# stm32_StepInveter_1904_01.net
KiCad netlist of a schematic drawn in EAGLE
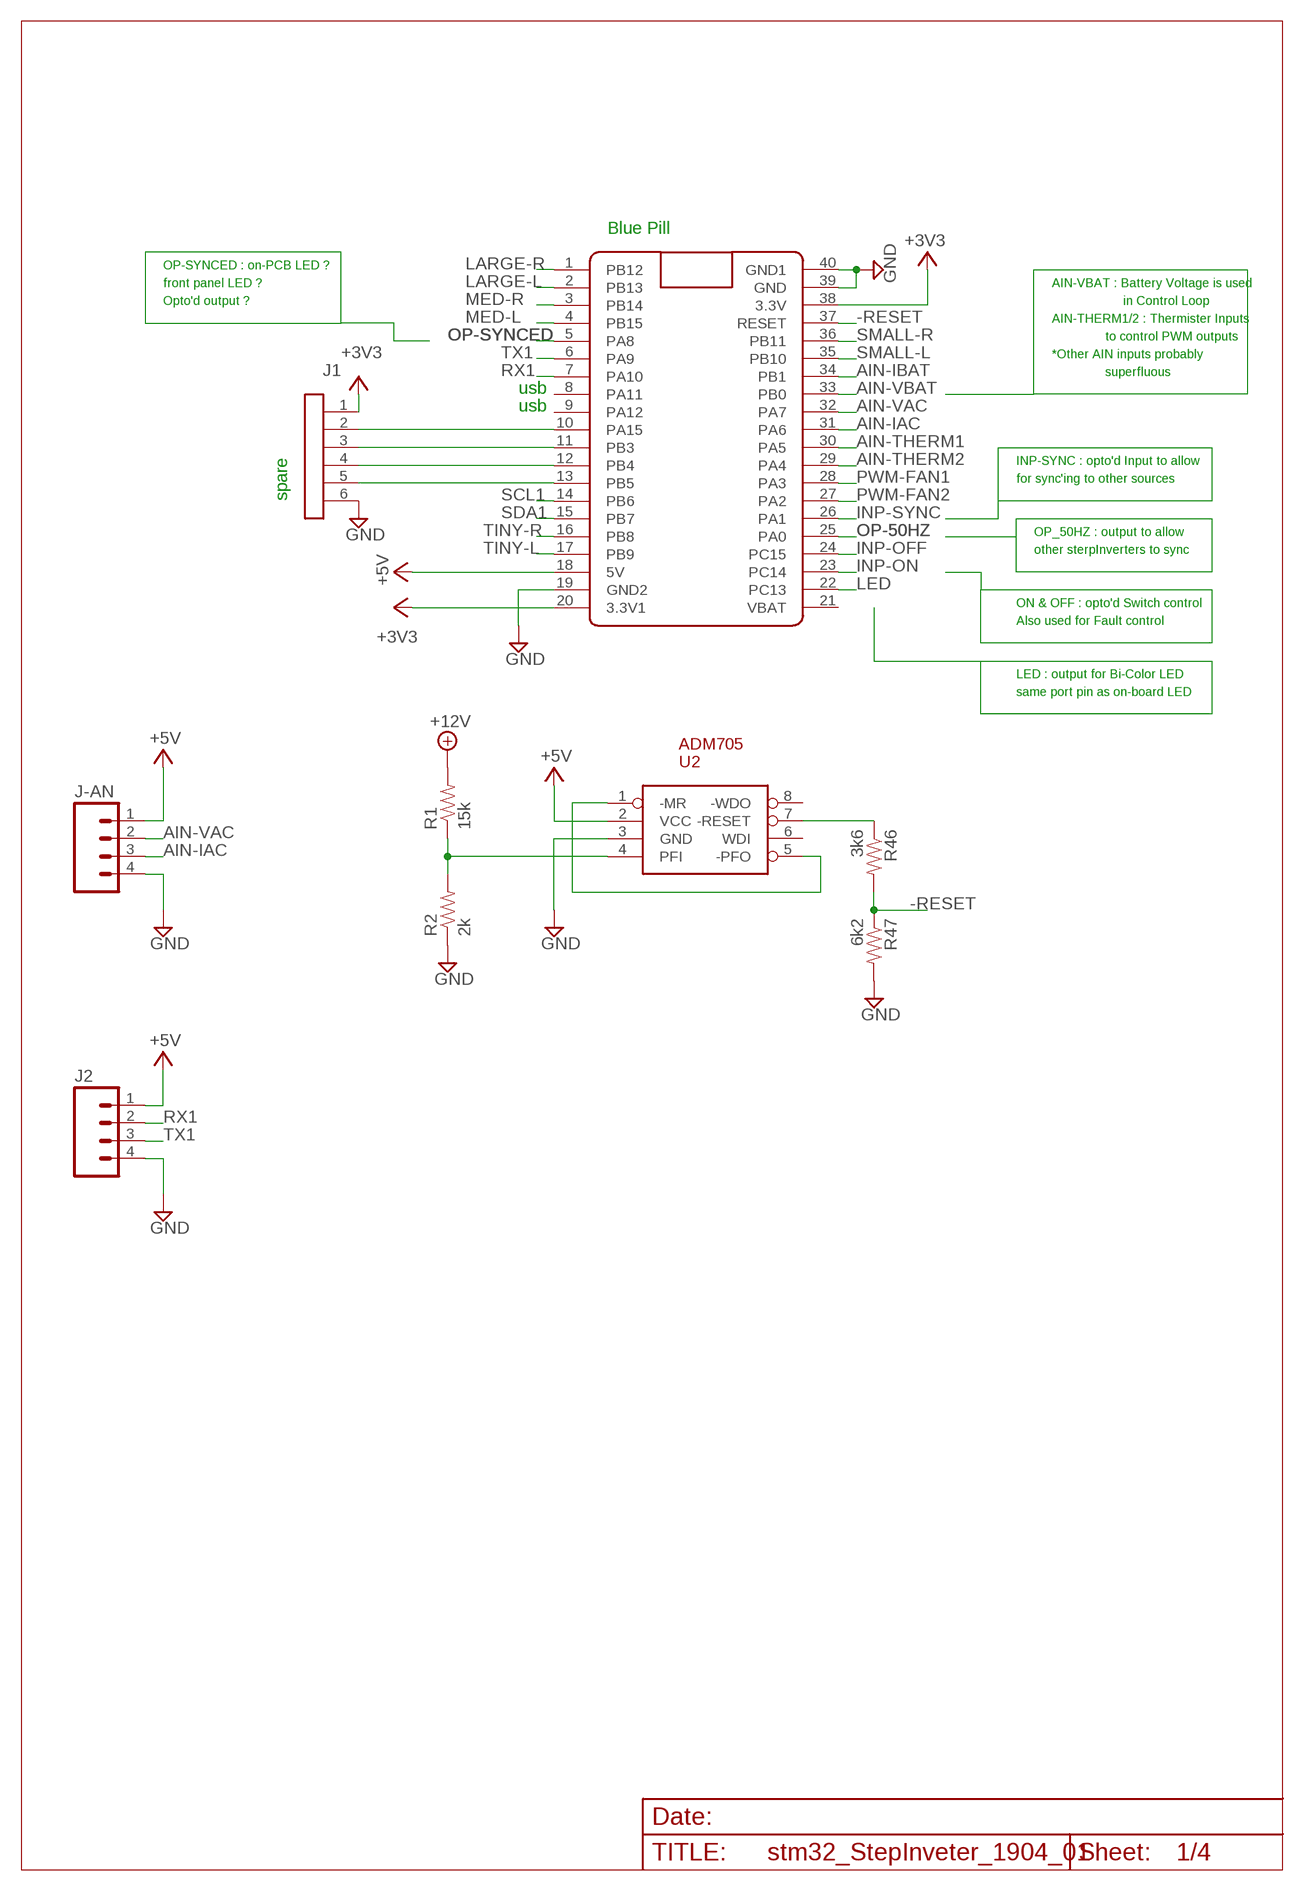
[diagram p0: schematic, sheet 1]
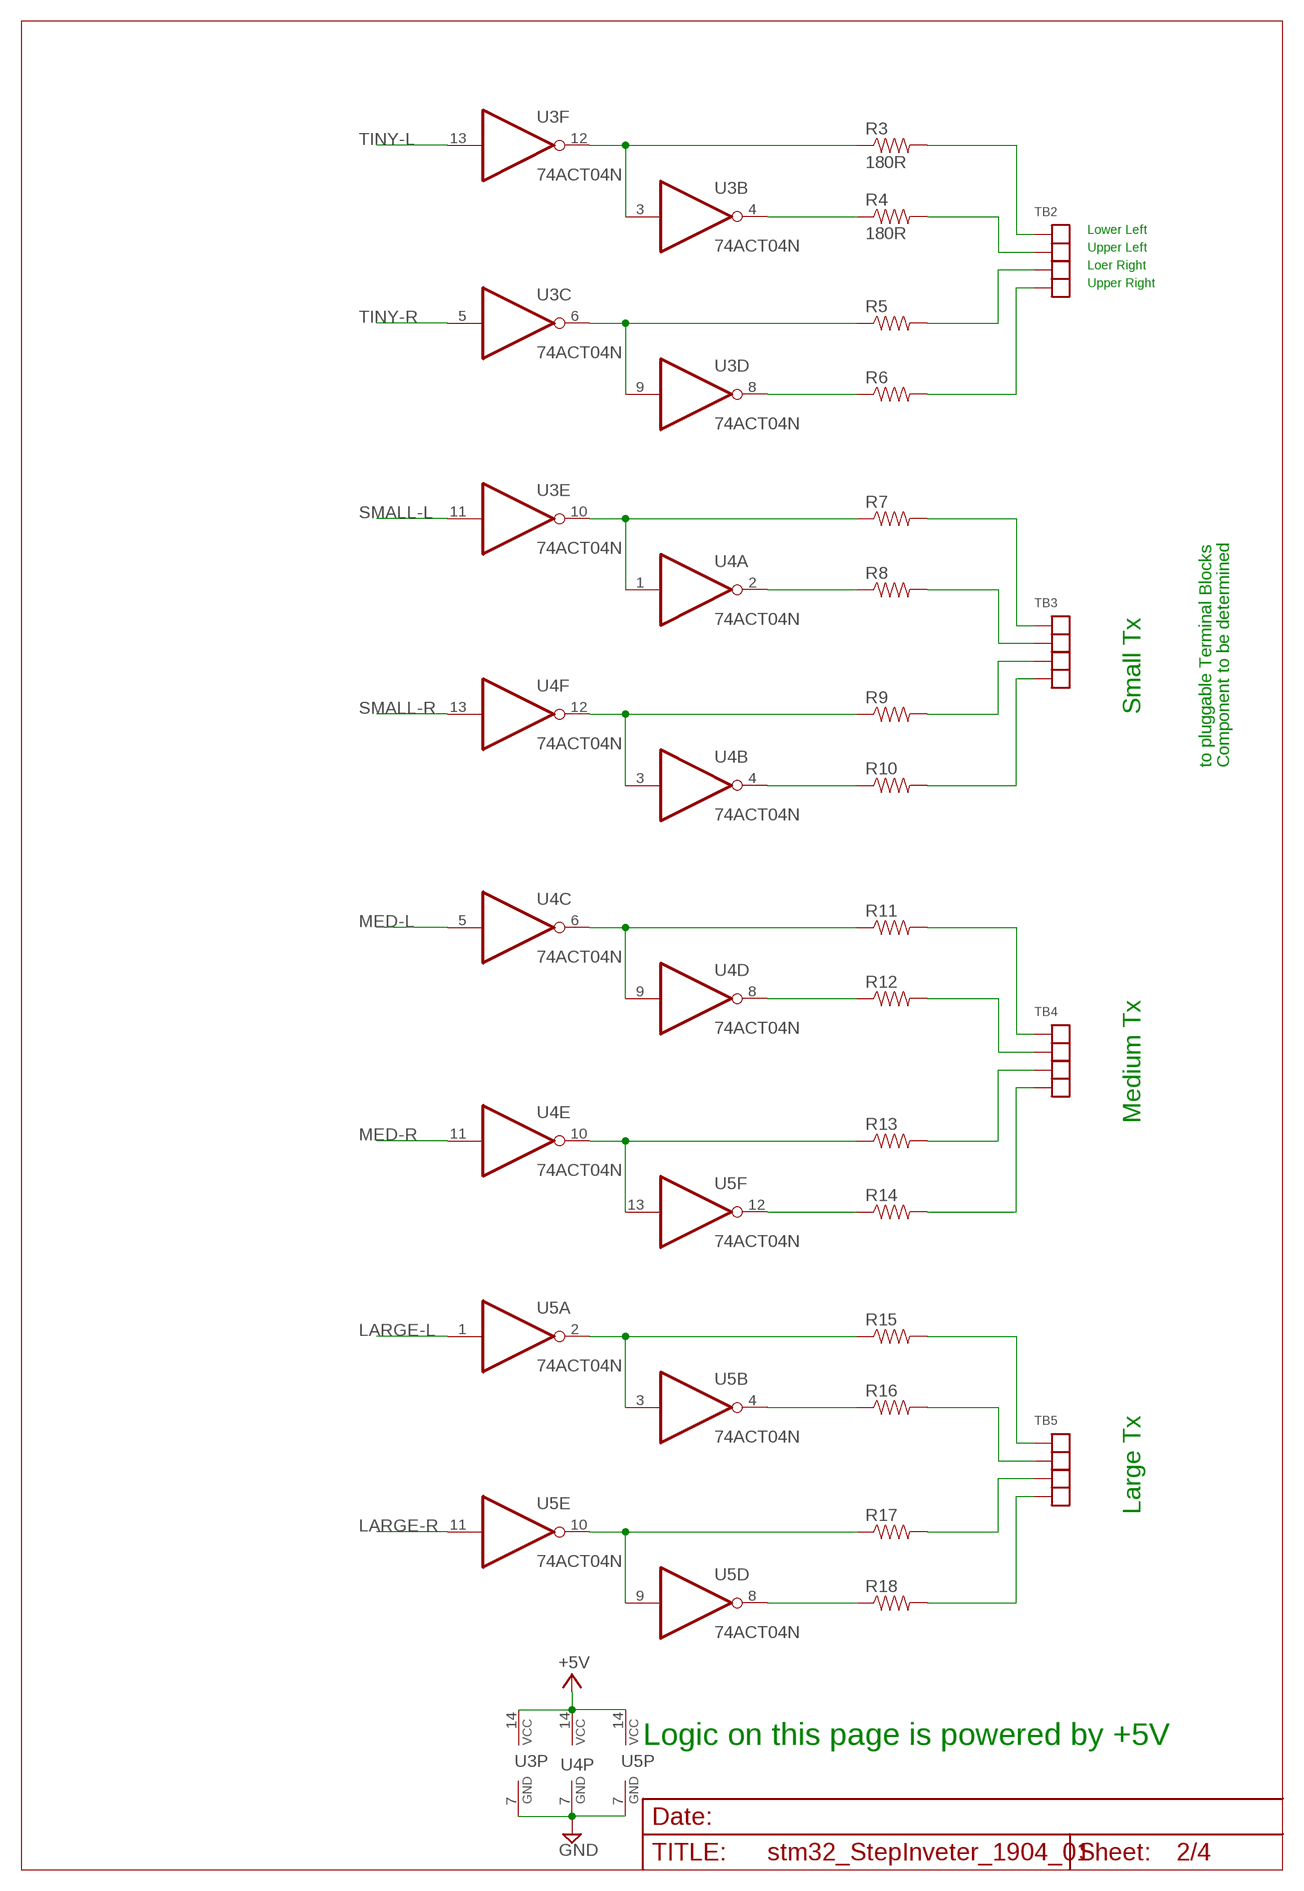
[diagram p1: schematic, sheet 2]
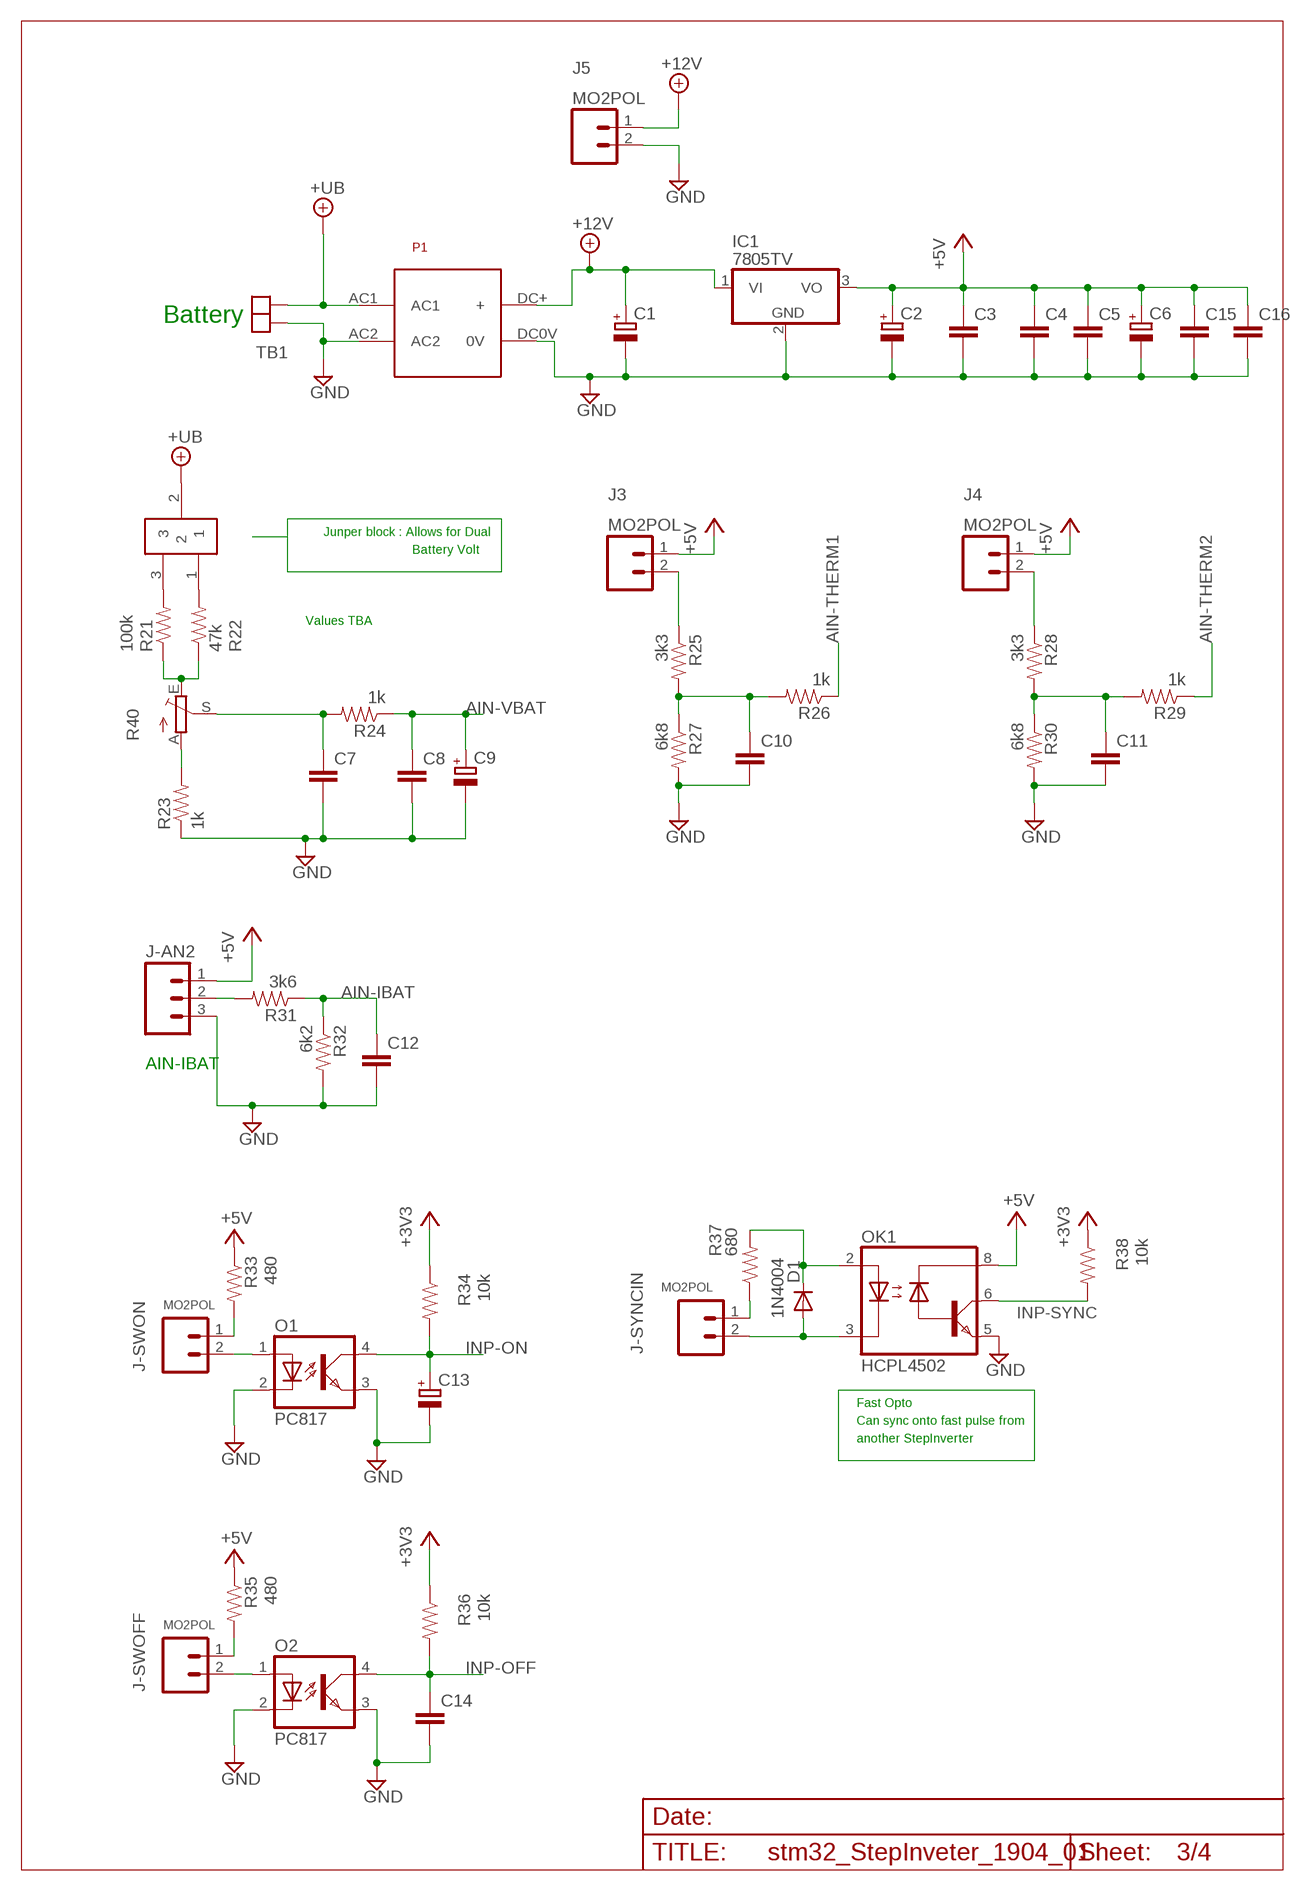
[diagram p2: schematic, sheet 3]
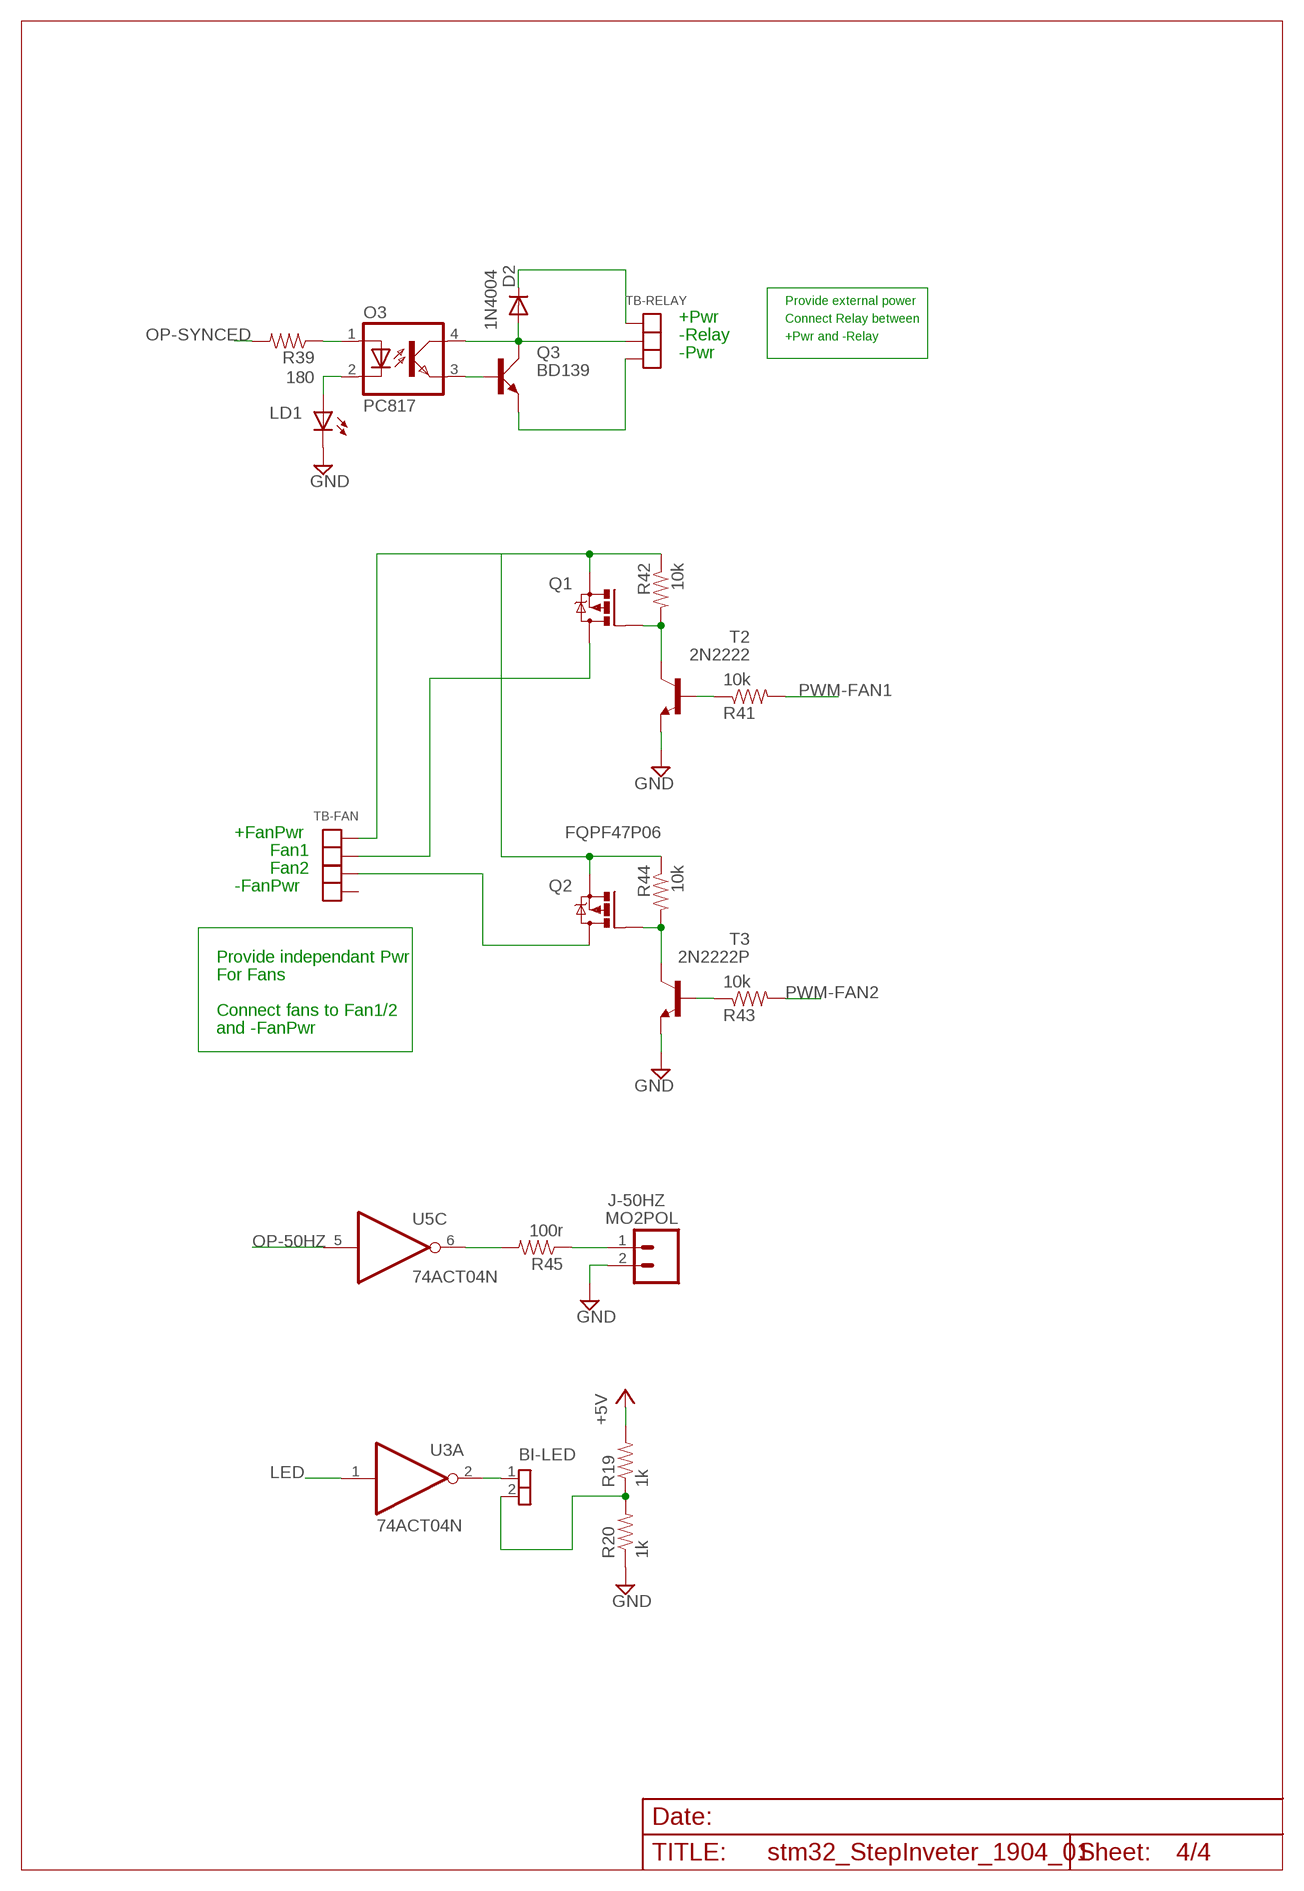
[diagram p3: schematic, sheet 4]

(export (version "E")
  (design (tool "Eeschema 10.0.6"))
  (components
    (comp (ref "J-AN")
      (value "SIL4")
      (footprint "eagle-import:SIL4")
      (libsource (lib "eagle-import") (part "SIL4"))
    )
    (comp (ref "J1")
      (value "SIL-6")
      (footprint "eagle-import:SIL6")
      (libsource (lib "eagle-import") (part "SIL-6"))
    )
    (comp (ref "J2")
      (value "SIL4")
      (footprint "eagle-import:SIL4")
      (libsource (lib "eagle-import") (part "SIL4"))
    )
    (comp (ref "R1")
      (value "15k")
      (footprint "eagle-import:AXIAL-0.4")
      (libsource (lib "eagle-import") (part "R4"))
    )
    (comp (ref "R2")
      (value "2k")
      (footprint "eagle-import:AXIAL-0.4")
      (libsource (lib "eagle-import") (part "R4"))
    )
    (comp (ref "R46")
      (value "3k6")
      (footprint "eagle-import:AXIAL-0.4")
      (libsource (lib "eagle-import") (part "R4"))
    )
    (comp (ref "R47")
      (value "6k2")
      (footprint "eagle-import:AXIAL-0.4")
      (libsource (lib "eagle-import") (part "R4"))
    )
    (comp (ref "U$1")
      (value "BLUE_PILL")
      (footprint "eagle-import:BLUE_PILL_CLEAN")
      (libsource (lib "eagle-import") (part "BLUE_PILL"))
    )
    (comp (ref "U2")
      (value "ADM705")
      (footprint "eagle-import:DIL08")
      (libsource (lib "eagle-import") (part "ADM705"))
    )
    (comp (ref "C1")
      (value "CPOL-EUE5-8.5")
      (footprint "eagle-import:E5-8,5")
      (libsource (lib "eagle-import") (part "CPOL-EUE5-8.5"))
    )
    (comp (ref "C2")
      (value "CPOL-EUE2.5-5")
      (footprint "eagle-import:E2,5-5")
      (libsource (lib "eagle-import") (part "CPOL-EUE2.5-5"))
    )
    (comp (ref "C3")
      (value "BCAP")
      (footprint "eagle-import:BCAP")
      (libsource (lib "eagle-import") (part "BCAP"))
    )
    (comp (ref "C4")
      (value "BCAP")
      (footprint "eagle-import:BCAP")
      (libsource (lib "eagle-import") (part "BCAP"))
    )
    (comp (ref "C5")
      (value "BCAP")
      (footprint "eagle-import:BCAP")
      (libsource (lib "eagle-import") (part "BCAP"))
    )
    (comp (ref "C6")
      (value "CPOL-EUE2.5-5")
      (footprint "eagle-import:E2,5-5")
      (libsource (lib "eagle-import") (part "CPOL-EUE2.5-5"))
    )
    (comp (ref "C7")
      (value "BCAP")
      (footprint "eagle-import:BCAP")
      (libsource (lib "eagle-import") (part "BCAP"))
    )
    (comp (ref "C8")
      (value "BCAP")
      (footprint "eagle-import:BCAP")
      (libsource (lib "eagle-import") (part "BCAP"))
    )
    (comp (ref "C9")
      (value "CPOL-EUE2.5-5")
      (footprint "eagle-import:E2,5-5")
      (libsource (lib "eagle-import") (part "CPOL-EUE2.5-5"))
    )
    (comp (ref "C10")
      (value "BCAP")
      (footprint "eagle-import:BCAP")
      (libsource (lib "eagle-import") (part "BCAP"))
    )
    (comp (ref "C11")
      (value "BCAP")
      (footprint "eagle-import:BCAP")
      (libsource (lib "eagle-import") (part "BCAP"))
    )
    (comp (ref "C12")
      (value "BCAP")
      (footprint "eagle-import:BCAP")
      (libsource (lib "eagle-import") (part "BCAP"))
    )
    (comp (ref "C13")
      (value "CPOL-EUE2.5-6")
      (footprint "eagle-import:E2,5-6")
      (libsource (lib "eagle-import") (part "CPOL-EUE2.5-6"))
    )
    (comp (ref "C14")
      (value "BCAP")
      (footprint "eagle-import:BCAP")
      (libsource (lib "eagle-import") (part "BCAP"))
    )
    (comp (ref "C15")
      (value "BCAP")
      (footprint "eagle-import:BCAP")
      (libsource (lib "eagle-import") (part "BCAP"))
    )
    (comp (ref "C16")
      (value "BCAP")
      (footprint "eagle-import:BCAP")
      (libsource (lib "eagle-import") (part "BCAP"))
    )
    (comp (ref "D1")
      (value "1N4004")
      (footprint "eagle-import:DO41-10")
      (libsource (lib "eagle-import") (part "1N4004"))
    )
    (comp (ref "IC1")
      (value "7805TV")
      (footprint "eagle-import:TO220V")
      (libsource (lib "eagle-import") (part "78TV05"))
    )
    (comp (ref "J-AN2")
      (value "MO3POL")
      (footprint "eagle-import:MOLEX-3")
      (libsource (lib "eagle-import") (part "MO3POL"))
    )
    (comp (ref "J-SWOFF")
      (value "MO2POL")
      (footprint "eagle-import:MOLEX-1X2")
      (libsource (lib "eagle-import") (part "MO2POL"))
    )
    (comp (ref "J-SWON")
      (value "MO2POL")
      (footprint "eagle-import:MOLEX-1X2")
      (libsource (lib "eagle-import") (part "MO2POL"))
    )
    (comp (ref "J-SYNCIN")
      (value "MO2POL")
      (footprint "eagle-import:MOLEX-1X2")
      (libsource (lib "eagle-import") (part "MO2POL"))
    )
    (comp (ref "J3")
      (value "MO2POL")
      (footprint "eagle-import:MOLEX-1X2")
      (libsource (lib "eagle-import") (part "MO2POL"))
    )
    (comp (ref "J4")
      (value "MO2POL")
      (footprint "eagle-import:MOLEX-1X2")
      (libsource (lib "eagle-import") (part "MO2POL"))
    )
    (comp (ref "J5")
      (value "MO2POL")
      (footprint "eagle-import:MOLEX-1X2")
      (libsource (lib "eagle-import") (part "MO2POL"))
    )
    (comp (ref "JP1")
      (value "JP1X3")
      (footprint "eagle-import:JP1X3")
      (libsource (lib "eagle-import") (part "JP1X3"))
    )
    (comp (ref "O1")
      (value "PC817")
      (footprint "eagle-import:DIL04")
      (fields (field (name "MPN") "PC817X4J000F"))
      (libsource (lib "eagle-import") (part "PC817"))
    )
    (comp (ref "O2")
      (value "PC817")
      (footprint "eagle-import:DIL04")
      (fields (field (name "MPN") "PC817X4J000F"))
      (libsource (lib "eagle-import") (part "PC817"))
    )
    (comp (ref "OK1")
      (value "HCPL4502")
      (footprint "eagle-import:DIL08")
      (fields (field (name "MF") "AGILENT TECHNOLOGIES") (field (name "MPN") "HCPL-4502-000E"))
      (libsource (lib "eagle-import") (part "HCPL4502"))
    )
    (comp (ref "P1")
      (value "ACDC")
      (footprint "eagle-import:ACDC")
      (libsource (lib "eagle-import") (part "ACDC"))
    )
    (comp (ref "R21")
      (value "100k")
      (footprint "eagle-import:AXIAL-0.4")
      (libsource (lib "eagle-import") (part "R4"))
    )
    (comp (ref "R22")
      (value "47k")
      (footprint "eagle-import:AXIAL-0.4")
      (libsource (lib "eagle-import") (part "R4"))
    )
    (comp (ref "R23")
      (value "1k")
      (footprint "eagle-import:AXIAL-0.4")
      (libsource (lib "eagle-import") (part "R4"))
    )
    (comp (ref "R24")
      (value "1k")
      (footprint "eagle-import:AXIAL-0.4")
      (libsource (lib "eagle-import") (part "R4"))
    )
    (comp (ref "R25")
      (value "3k3")
      (footprint "eagle-import:AXIAL-0.4")
      (libsource (lib "eagle-import") (part "R4"))
    )
    (comp (ref "R26")
      (value "1k")
      (footprint "eagle-import:AXIAL-0.4")
      (libsource (lib "eagle-import") (part "R4"))
    )
    (comp (ref "R27")
      (value "6k8")
      (footprint "eagle-import:AXIAL-0.4")
      (libsource (lib "eagle-import") (part "R4"))
    )
    (comp (ref "R28")
      (value "3k3")
      (footprint "eagle-import:AXIAL-0.4")
      (libsource (lib "eagle-import") (part "R4"))
    )
    (comp (ref "R29")
      (value "1k")
      (footprint "eagle-import:AXIAL-0.4")
      (libsource (lib "eagle-import") (part "R4"))
    )
    (comp (ref "R30")
      (value "6k8")
      (footprint "eagle-import:AXIAL-0.4")
      (libsource (lib "eagle-import") (part "R4"))
    )
    (comp (ref "R31")
      (value "3k6")
      (footprint "eagle-import:AXIAL-0.4")
      (libsource (lib "eagle-import") (part "R4"))
    )
    (comp (ref "R32")
      (value "6k2")
      (footprint "eagle-import:AXIAL-0.4")
      (libsource (lib "eagle-import") (part "R4"))
    )
    (comp (ref "R33")
      (value "480")
      (footprint "eagle-import:AXIAL-0.4")
      (libsource (lib "eagle-import") (part "R4"))
    )
    (comp (ref "R34")
      (value "10k")
      (footprint "eagle-import:AXIAL-0.4")
      (libsource (lib "eagle-import") (part "R4"))
    )
    (comp (ref "R35")
      (value "480")
      (footprint "eagle-import:AXIAL-0.4")
      (libsource (lib "eagle-import") (part "R4"))
    )
    (comp (ref "R36")
      (value "10k")
      (footprint "eagle-import:AXIAL-0.4")
      (libsource (lib "eagle-import") (part "R4"))
    )
    (comp (ref "R37")
      (value "680")
      (footprint "eagle-import:AXIAL-0.4")
      (libsource (lib "eagle-import") (part "R4"))
    )
    (comp (ref "R38")
      (value "10k")
      (footprint "eagle-import:AXIAL-0.4")
      (libsource (lib "eagle-import") (part "R4"))
    )
    (comp (ref "R40")
      (value "TRIM_EU-B64Y")
      (footprint "eagle-import:B64Y")
      (libsource (lib "eagle-import") (part "TRIM_EU-B64Y"))
    )
    (comp (ref "TB1")
      (value "TB2381")
      (footprint "eagle-import:TB-KF2EDG381-2P")
      (libsource (lib "eagle-import") (part "TB2381"))
    )
    (comp (ref "BI-LED")
      (value "SIL-2")
      (footprint "eagle-import:JP1")
      (libsource (lib "eagle-import") (part "SIL-2"))
    )
    (comp (ref "D2")
      (value "1N4004")
      (footprint "eagle-import:DO41-10")
      (libsource (lib "eagle-import") (part "1N4004"))
    )
    (comp (ref "J-50HZ")
      (value "MO2POL")
      (footprint "eagle-import:MOLEX-1X2")
      (libsource (lib "eagle-import") (part "MO2POL"))
    )
    (comp (ref "LD1")
      (value "LED3MM")
      (footprint "eagle-import:LED3MM")
      (libsource (lib "eagle-import") (part "LED3MM"))
    )
    (comp (ref "O3")
      (value "PC817")
      (footprint "eagle-import:DIL04")
      (fields (field (name "MPN") "PC817X4J000F"))
      (libsource (lib "eagle-import") (part "PC817"))
    )
    (comp (ref "Q1")
      (value "MOSFET-PCHFQPF47P06")
      (footprint "eagle-import:TO220BV")
      (libsource (lib "eagle-import") (part "MOSFET-PCHFQPF47P06"))
    )
    (comp (ref "Q2")
      (value "FQPF47P06")
      (footprint "eagle-import:TO220BV")
      (libsource (lib "eagle-import") (part "MOSFET-PCHFQPF47P06"))
    )
    (comp (ref "Q3")
      (value "BD139")
      (footprint "eagle-import:TO126AV")
      (libsource (lib "eagle-import") (part "BD139"))
    )
    (comp (ref "R19")
      (value "1k")
      (footprint "eagle-import:AXIAL-0.4")
      (libsource (lib "eagle-import") (part "R4"))
    )
    (comp (ref "R20")
      (value "1k")
      (footprint "eagle-import:AXIAL-0.4")
      (libsource (lib "eagle-import") (part "R4"))
    )
    (comp (ref "R39")
      (value "180")
      (footprint "eagle-import:AXIAL-0.4")
      (libsource (lib "eagle-import") (part "R4"))
    )
    (comp (ref "R41")
      (value "10k")
      (footprint "eagle-import:AXIAL-0.4")
      (libsource (lib "eagle-import") (part "R4"))
    )
    (comp (ref "R42")
      (value "10k")
      (footprint "eagle-import:AXIAL-0.4")
      (libsource (lib "eagle-import") (part "R4"))
    )
    (comp (ref "R43")
      (value "10k")
      (footprint "eagle-import:AXIAL-0.4")
      (libsource (lib "eagle-import") (part "R4"))
    )
    (comp (ref "R44")
      (value "10k")
      (footprint "eagle-import:AXIAL-0.4")
      (libsource (lib "eagle-import") (part "R4"))
    )
    (comp (ref "R45")
      (value "100r")
      (footprint "eagle-import:AXIAL-0.4")
      (libsource (lib "eagle-import") (part "R4"))
    )
    (comp (ref "T2")
      (value "2N2222")
      (footprint "eagle-import:TO92_")
      (libsource (lib "eagle-import") (part "2N2222P"))
    )
    (comp (ref "T3")
      (value "2N2222P")
      (footprint "eagle-import:TO92_")
      (libsource (lib "eagle-import") (part "2N2222P"))
    )
    (comp (ref "TB-FAN")
      (value "TB4")
      (footprint "eagle-import:TB-KF2EDG381-4P")
      (libsource (lib "eagle-import") (part "TB4"))
    )
    (comp (ref "TB-RELAY")
      (value "TB3381")
      (footprint "eagle-import:TB-KF2EDG381-3P")
      (libsource (lib "eagle-import") (part "TB3381"))
    )
    (comp (ref "U3")
      (value "74ACT04N")
      (footprint "eagle-import:DIL14")
      (libsource (lib "eagle-import") (part "7404NACT"))
    )
    (comp (ref "U5")
      (value "74ACT04N")
      (footprint "eagle-import:DIL14")
      (libsource (lib "eagle-import") (part "7404NACT"))
    )
    (comp (ref "R3")
      (value "180R")
      (footprint "eagle-import:AXIAL-0.4")
      (libsource (lib "eagle-import") (part "R4"))
    )
    (comp (ref "R4")
      (value "180R")
      (footprint "eagle-import:AXIAL-0.4")
      (libsource (lib "eagle-import") (part "R4"))
    )
    (comp (ref "R5")
      (value "R4")
      (footprint "eagle-import:AXIAL-0.4")
      (libsource (lib "eagle-import") (part "R4"))
    )
    (comp (ref "R6")
      (value "R4")
      (footprint "eagle-import:AXIAL-0.4")
      (libsource (lib "eagle-import") (part "R4"))
    )
    (comp (ref "R7")
      (value "R4")
      (footprint "eagle-import:AXIAL-0.4")
      (libsource (lib "eagle-import") (part "R4"))
    )
    (comp (ref "R8")
      (value "R4")
      (footprint "eagle-import:AXIAL-0.4")
      (libsource (lib "eagle-import") (part "R4"))
    )
    (comp (ref "R9")
      (value "R4")
      (footprint "eagle-import:AXIAL-0.4")
      (libsource (lib "eagle-import") (part "R4"))
    )
    (comp (ref "R10")
      (value "R4")
      (footprint "eagle-import:AXIAL-0.4")
      (libsource (lib "eagle-import") (part "R4"))
    )
    (comp (ref "R11")
      (value "R4")
      (footprint "eagle-import:AXIAL-0.4")
      (libsource (lib "eagle-import") (part "R4"))
    )
    (comp (ref "R12")
      (value "R4")
      (footprint "eagle-import:AXIAL-0.4")
      (libsource (lib "eagle-import") (part "R4"))
    )
    (comp (ref "R13")
      (value "R4")
      (footprint "eagle-import:AXIAL-0.4")
      (libsource (lib "eagle-import") (part "R4"))
    )
    (comp (ref "R14")
      (value "R4")
      (footprint "eagle-import:AXIAL-0.4")
      (libsource (lib "eagle-import") (part "R4"))
    )
    (comp (ref "R15")
      (value "R4")
      (footprint "eagle-import:AXIAL-0.4")
      (libsource (lib "eagle-import") (part "R4"))
    )
    (comp (ref "R16")
      (value "R4")
      (footprint "eagle-import:AXIAL-0.4")
      (libsource (lib "eagle-import") (part "R4"))
    )
    (comp (ref "R17")
      (value "R4")
      (footprint "eagle-import:AXIAL-0.4")
      (libsource (lib "eagle-import") (part "R4"))
    )
    (comp (ref "R18")
      (value "R4")
      (footprint "eagle-import:AXIAL-0.4")
      (libsource (lib "eagle-import") (part "R4"))
    )
    (comp (ref "TB2")
      (value "TB4381_SIL")
      (footprint "eagle-import:TB-381-SIL-4P")
      (libsource (lib "eagle-import") (part "TB4381_SIL"))
    )
    (comp (ref "TB3")
      (value "TB4381_SIL")
      (footprint "eagle-import:TB-381-SIL-4P")
      (libsource (lib "eagle-import") (part "TB4381_SIL"))
    )
    (comp (ref "TB4")
      (value "TB4381_SIL")
      (footprint "eagle-import:TB-381-SIL-4P")
      (libsource (lib "eagle-import") (part "TB4381_SIL"))
    )
    (comp (ref "TB5")
      (value "TB4381_SIL")
      (footprint "eagle-import:TB-381-SIL-4P")
      (libsource (lib "eagle-import") (part "TB4381_SIL"))
    )
    (comp (ref "U4")
      (value "74ACT04N")
      (footprint "eagle-import:DIL14")
      (libsource (lib "eagle-import") (part "7404NACT"))
    )
  )
  (nets
    (net (code "1") (name "+3V3") (class "Default")
      (node (ref "J1") (pin "1") (pinfunction "P$1_1") (pintype "bidirectional"))
      (node (ref "R34") (pin "P$1") (pinfunction "1_P$1") (pintype "passive"))
      (node (ref "R36") (pin "P$1") (pinfunction "1_P$1") (pintype "passive"))
      (node (ref "R38") (pin "P$1") (pinfunction "1_P$1") (pintype "passive"))
      (node (ref "U$1") (pin "20") (pinfunction "3.3V1_20") (pintype "bidirectional"))
      (node (ref "U$1") (pin "38") (pinfunction "3.3V_38") (pintype "bidirectional"))
    )
    (net (code "2") (name "+5V") (class "Default")
      (node (ref "C15") (pin "1") (pinfunction "1_1") (pintype "passive"))
      (node (ref "C16") (pin "1") (pinfunction "1_1") (pintype "passive"))
      (node (ref "C2") (pin "+") (pinfunction "+_+") (pintype "passive"))
      (node (ref "C3") (pin "1") (pinfunction "1_1") (pintype "passive"))
      (node (ref "C4") (pin "1") (pinfunction "1_1") (pintype "passive"))
      (node (ref "C5") (pin "1") (pinfunction "1_1") (pintype "passive"))
      (node (ref "C6") (pin "+") (pinfunction "+_+") (pintype "passive"))
      (node (ref "IC1") (pin "3") (pinfunction "VO_3") (pintype "passive"))
      (node (ref "J-AN") (pin "1") (pinfunction "1_1") (pintype "passive"))
      (node (ref "J-AN2") (pin "1") (pinfunction "1_1") (pintype "passive"))
      (node (ref "J2") (pin "1") (pinfunction "1_1") (pintype "passive"))
      (node (ref "J3") (pin "1") (pinfunction "1_1") (pintype "passive"))
      (node (ref "J4") (pin "1") (pinfunction "1_1") (pintype "passive"))
      (node (ref "OK1") (pin "8") (pinfunction "VCC_8") (pintype "passive"))
      (node (ref "R19") (pin "P$2") (pinfunction "2_P$2") (pintype "passive"))
      (node (ref "R33") (pin "P$1") (pinfunction "1_P$1") (pintype "passive"))
      (node (ref "R35") (pin "P$1") (pinfunction "1_P$1") (pintype "passive"))
      (node (ref "U$1") (pin "18") (pinfunction "5V_18") (pintype "bidirectional"))
      (node (ref "U2") (pin "2") (pinfunction "VCC_2") (pintype "bidirectional"))
      (node (ref "U3") (pin "14") (pinfunction "VCC_14") (pintype "power_in"))
      (node (ref "U4") (pin "14") (pinfunction "VCC_14") (pintype "power_in"))
      (node (ref "U5") (pin "14") (pinfunction "VCC_14") (pintype "power_in"))
    )
    (net (code "3") (name "+12V") (class "Default")
      (node (ref "C1") (pin "+") (pinfunction "+_+") (pintype "passive"))
      (node (ref "IC1") (pin "1") (pinfunction "VI_1") (pintype "input"))
      (node (ref "J5") (pin "1") (pinfunction "1_1") (pintype "passive"))
      (node (ref "P1") (pin "DC+") (pinfunction "+_DC+") (pintype "bidirectional"))
      (node (ref "R1") (pin "P$2") (pinfunction "2_P$2") (pintype "passive"))
    )
    (net (code "4") (name "+UB") (class "Default")
      (node (ref "JP1") (pin "2") (pinfunction "2_2") (pintype "bidirectional"))
      (node (ref "P1") (pin "AC1") (pinfunction "AC1_AC1") (pintype "bidirectional"))
      (node (ref "TB1") (pin "1") (pinfunction "1_1") (pintype "bidirectional"))
    )
    (net (code "5") (name "-RESET") (class "Default")
      (node (ref "R46") (pin "P$2") (pinfunction "2_P$2") (pintype "passive"))
      (node (ref "R47") (pin "P$1") (pinfunction "1_P$1") (pintype "passive"))
      (node (ref "U$1") (pin "37") (pinfunction "RESET_37") (pintype "bidirectional"))
    )
    (net (code "6") (name "AIN-IAC") (class "Default")
      (node (ref "J-AN") (pin "3") (pinfunction "3_3") (pintype "passive"))
      (node (ref "U$1") (pin "31") (pinfunction "PA6_31") (pintype "bidirectional"))
    )
    (net (code "7") (name "AIN-IBAT") (class "Default")
      (node (ref "C12") (pin "1") (pinfunction "1_1") (pintype "passive"))
      (node (ref "R31") (pin "P$1") (pinfunction "1_P$1") (pintype "passive"))
      (node (ref "R32") (pin "P$1") (pinfunction "1_P$1") (pintype "passive"))
      (node (ref "U$1") (pin "34") (pinfunction "PB1_34") (pintype "bidirectional"))
    )
    (net (code "8") (name "AIN-THERM1") (class "Default")
      (node (ref "R26") (pin "P$1") (pinfunction "1_P$1") (pintype "passive"))
      (node (ref "U$1") (pin "30") (pinfunction "PA5_30") (pintype "bidirectional"))
    )
    (net (code "9") (name "AIN-THERM2") (class "Default")
      (node (ref "R29") (pin "P$1") (pinfunction "1_P$1") (pintype "passive"))
      (node (ref "U$1") (pin "29") (pinfunction "PA4_29") (pintype "bidirectional"))
    )
    (net (code "10") (name "AIN-VAC") (class "Default")
      (node (ref "J-AN") (pin "2") (pinfunction "2_2") (pintype "passive"))
      (node (ref "U$1") (pin "32") (pinfunction "PA7_32") (pintype "bidirectional"))
    )
    (net (code "11") (name "AIN-VBAT") (class "Default")
      (node (ref "C8") (pin "1") (pinfunction "1_1") (pintype "passive"))
      (node (ref "C9") (pin "+") (pinfunction "+_+") (pintype "passive"))
      (node (ref "R24") (pin "P$1") (pinfunction "1_P$1") (pintype "passive"))
      (node (ref "U$1") (pin "33") (pinfunction "PB0_33") (pintype "bidirectional"))
    )
    (net (code "12") (name "GND") (class "Default")
      (node (ref "C1") (pin "-") (pinfunction "-_-") (pintype "passive"))
      (node (ref "C10") (pin "2") (pinfunction "2_2") (pintype "passive"))
      (node (ref "C11") (pin "2") (pinfunction "2_2") (pintype "passive"))
      (node (ref "C12") (pin "2") (pinfunction "2_2") (pintype "passive"))
      (node (ref "C13") (pin "-") (pinfunction "-_-") (pintype "passive"))
      (node (ref "C14") (pin "2") (pinfunction "2_2") (pintype "passive"))
      (node (ref "C15") (pin "2") (pinfunction "2_2") (pintype "passive"))
      (node (ref "C16") (pin "2") (pinfunction "2_2") (pintype "passive"))
      (node (ref "C2") (pin "-") (pinfunction "-_-") (pintype "passive"))
      (node (ref "C3") (pin "2") (pinfunction "2_2") (pintype "passive"))
      (node (ref "C4") (pin "2") (pinfunction "2_2") (pintype "passive"))
      (node (ref "C5") (pin "2") (pinfunction "2_2") (pintype "passive"))
      (node (ref "C6") (pin "-") (pinfunction "-_-") (pintype "passive"))
      (node (ref "C7") (pin "2") (pinfunction "2_2") (pintype "passive"))
      (node (ref "C8") (pin "2") (pinfunction "2_2") (pintype "passive"))
      (node (ref "C9") (pin "-") (pinfunction "-_-") (pintype "passive"))
      (node (ref "IC1") (pin "2") (pinfunction "GND_2") (pintype "passive"))
      (node (ref "J-50HZ") (pin "2") (pinfunction "2_2") (pintype "passive"))
      (node (ref "J-AN") (pin "4") (pinfunction "4_4") (pintype "passive"))
      (node (ref "J-AN2") (pin "3") (pinfunction "3_3") (pintype "passive"))
      (node (ref "J1") (pin "6") (pinfunction "P$6_6") (pintype "bidirectional"))
      (node (ref "J2") (pin "4") (pinfunction "4_4") (pintype "passive"))
      (node (ref "J5") (pin "2") (pinfunction "2_2") (pintype "passive"))
      (node (ref "LD1") (pin "K") (pinfunction "C_K") (pintype "passive"))
      (node (ref "O1") (pin "2") (pinfunction "C_2") (pintype "passive"))
      (node (ref "O1") (pin "3") (pinfunction "EMIT_3") (pintype "passive"))
      (node (ref "O2") (pin "2") (pinfunction "C_2") (pintype "passive"))
      (node (ref "O2") (pin "3") (pinfunction "EMIT_3") (pintype "passive"))
      (node (ref "OK1") (pin "5") (pinfunction "GND_5") (pintype "passive"))
      (node (ref "P1") (pin "AC2") (pinfunction "AC2_AC2") (pintype "bidirectional"))
      (node (ref "P1") (pin "DC0V") (pinfunction "0V_DC0V") (pintype "bidirectional"))
      (node (ref "R2") (pin "P$1") (pinfunction "1_P$1") (pintype "passive"))
      (node (ref "R20") (pin "P$1") (pinfunction "1_P$1") (pintype "passive"))
      (node (ref "R23") (pin "P$1") (pinfunction "1_P$1") (pintype "passive"))
      (node (ref "R27") (pin "P$2") (pinfunction "2_P$2") (pintype "passive"))
      (node (ref "R30") (pin "P$2") (pinfunction "2_P$2") (pintype "passive"))
      (node (ref "R32") (pin "P$2") (pinfunction "2_P$2") (pintype "passive"))
      (node (ref "R47") (pin "P$2") (pinfunction "2_P$2") (pintype "passive"))
      (node (ref "T2") (pin "1") (pinfunction "E_1") (pintype "passive"))
      (node (ref "T3") (pin "1") (pinfunction "E_1") (pintype "passive"))
      (node (ref "TB1") (pin "2") (pinfunction "2_2") (pintype "bidirectional"))
      (node (ref "U$1") (pin "19") (pinfunction "GND2_19") (pintype "bidirectional"))
      (node (ref "U$1") (pin "39") (pinfunction "GND_39") (pintype "bidirectional"))
      (node (ref "U$1") (pin "40") (pinfunction "GND1_40") (pintype "power_in"))
      (node (ref "U2") (pin "3") (pinfunction "GND_3") (pintype "bidirectional"))
      (node (ref "U3") (pin "7") (pinfunction "GND_7") (pintype "power_in"))
      (node (ref "U4") (pin "7") (pinfunction "GND_7") (pintype "power_in"))
      (node (ref "U5") (pin "7") (pinfunction "GND_7") (pintype "power_in"))
    )
    (net (code "13") (name "INP-OFF") (class "Default")
      (node (ref "C14") (pin "1") (pinfunction "1_1") (pintype "passive"))
      (node (ref "O2") (pin "4") (pinfunction "COL_4") (pintype "passive"))
      (node (ref "R36") (pin "P$2") (pinfunction "2_P$2") (pintype "passive"))
      (node (ref "U$1") (pin "24") (pinfunction "PC15_24") (pintype "bidirectional"))
    )
    (net (code "14") (name "INP-ON") (class "Default")
      (node (ref "C13") (pin "+") (pinfunction "+_+") (pintype "passive"))
      (node (ref "O1") (pin "4") (pinfunction "COL_4") (pintype "passive"))
      (node (ref "R34") (pin "P$2") (pinfunction "2_P$2") (pintype "passive"))
      (node (ref "U$1") (pin "23") (pinfunction "PC14_23") (pintype "bidirectional"))
    )
    (net (code "15") (name "INP-SYNC") (class "Default")
      (node (ref "OK1") (pin "6") (pinfunction "VO_6") (pintype "passive"))
      (node (ref "R38") (pin "P$2") (pinfunction "2_P$2") (pintype "passive"))
      (node (ref "U$1") (pin "26") (pinfunction "PA1_26") (pintype "bidirectional"))
    )
    (net (code "16") (name "LARGE-L") (class "Default")
      (node (ref "U$1") (pin "2") (pinfunction "PB13_2") (pintype "bidirectional"))
      (node (ref "U5") (pin "1") (pinfunction "I_1") (pintype "input"))
    )
    (net (code "17") (name "LARGE-R") (class "Default")
      (node (ref "U$1") (pin "1") (pinfunction "PB12_1") (pintype "bidirectional"))
      (node (ref "U5") (pin "11") (pinfunction "I_11") (pintype "input"))
    )
    (net (code "18") (name "LED") (class "Default")
      (node (ref "U$1") (pin "22") (pinfunction "PC13_22") (pintype "bidirectional"))
      (node (ref "U3") (pin "1") (pinfunction "I_1") (pintype "input"))
    )
    (net (code "19") (name "MED-L") (class "Default")
      (node (ref "U$1") (pin "4") (pinfunction "PB15_4") (pintype "bidirectional"))
      (node (ref "U4") (pin "5") (pinfunction "I_5") (pintype "input"))
    )
    (net (code "20") (name "MED-R") (class "Default")
      (node (ref "U$1") (pin "3") (pinfunction "PB14_3") (pintype "bidirectional"))
      (node (ref "U4") (pin "11") (pinfunction "I_11") (pintype "input"))
    )
    (net (code "21") (name "Net-(D2-PadC)") (class "Default")
      (node (ref "D2") (pin "C") (pinfunction "C_C") (pintype "passive"))
      (node (ref "TB-RELAY") (pin "1") (pinfunction "1_1") (pintype "bidirectional"))
    )
    (net (code "22") (name "Net-(J1-P$2)") (class "Default")
      (node (ref "J1") (pin "2") (pinfunction "P$2_2") (pintype "bidirectional"))
      (node (ref "U$1") (pin "10") (pinfunction "PA15_10") (pintype "bidirectional"))
    )
    (net (code "23") (name "Net-(J1-P$3)") (class "Default")
      (node (ref "J1") (pin "3") (pinfunction "P$3_3") (pintype "bidirectional"))
      (node (ref "U$1") (pin "11") (pinfunction "PB3_11") (pintype "bidirectional"))
    )
    (net (code "24") (name "Net-(J1-P$4)") (class "Default")
      (node (ref "J1") (pin "4") (pinfunction "P$4_4") (pintype "bidirectional"))
      (node (ref "U$1") (pin "12") (pinfunction "PB4_12") (pintype "bidirectional"))
    )
    (net (code "25") (name "Net-(J1-P$5)") (class "Default")
      (node (ref "J1") (pin "5") (pinfunction "P$5_5") (pintype "bidirectional"))
      (node (ref "U$1") (pin "13") (pinfunction "PB5_13") (pintype "bidirectional"))
    )
    (net (code "26") (name "Net-(O1-A)") (class "Default")
      (node (ref "J-SWON") (pin "2") (pinfunction "2_2") (pintype "passive"))
      (node (ref "O1") (pin "1") (pinfunction "A_1") (pintype "passive"))
    )
    (net (code "27") (name "Net-(O2-A)") (class "Default")
      (node (ref "J-SWOFF") (pin "2") (pinfunction "2_2") (pintype "passive"))
      (node (ref "O2") (pin "1") (pinfunction "A_1") (pintype "passive"))
    )
    (net (code "28") (name "Net-(O3-A)") (class "Default")
      (node (ref "O3") (pin "1") (pinfunction "A_1") (pintype "passive"))
      (node (ref "R39") (pin "P$1") (pinfunction "1_P$1") (pintype "passive"))
    )
    (net (code "29") (name "Net-(O3-C)") (class "Default")
      (node (ref "LD1") (pin "A") (pinfunction "A_A") (pintype "passive"))
      (node (ref "O3") (pin "2") (pinfunction "C_2") (pintype "passive"))
    )
    (net (code "30") (name "Net-(O3-COL)") (class "Default")
      (node (ref "D2") (pin "A") (pinfunction "A_A") (pintype "passive"))
      (node (ref "O3") (pin "4") (pinfunction "COL_4") (pintype "passive"))
      (node (ref "Q3") (pin "C") (pinfunction "C_C") (pintype "passive"))
      (node (ref "TB-RELAY") (pin "2") (pinfunction "2_2") (pintype "bidirectional"))
    )
    (net (code "31") (name "Net-(O3-EMIT)") (class "Default")
      (node (ref "O3") (pin "3") (pinfunction "EMIT_3") (pintype "passive"))
      (node (ref "Q3") (pin "B") (pinfunction "B_B") (pintype "passive"))
    )
    (net (code "32") (name "Net-(OK1-A)") (class "Default")
      (node (ref "D1") (pin "C") (pinfunction "C_C") (pintype "passive"))
      (node (ref "OK1") (pin "2") (pinfunction "A_2") (pintype "passive"))
      (node (ref "R37") (pin "P$2") (pinfunction "2_P$2") (pintype "passive"))
    )
    (net (code "33") (name "Net-(OK1-C)") (class "Default")
      (node (ref "D1") (pin "A") (pinfunction "A_A") (pintype "passive"))
      (node (ref "J-SYNCIN") (pin "2") (pinfunction "2_2") (pintype "passive"))
      (node (ref "OK1") (pin "3") (pinfunction "C_3") (pintype "passive"))
    )
    (net (code "34") (name "Net-(Q1-PadD)") (class "Default")
      (node (ref "Q1") (pin "D") (pinfunction "D_D") (pintype "passive"))
      (node (ref "TB-FAN") (pin "2") (pinfunction "2_2") (pintype "bidirectional"))
    )
    (net (code "35") (name "Net-(Q2-PadD)") (class "Default")
      (node (ref "Q2") (pin "D") (pinfunction "D_D") (pintype "passive"))
      (node (ref "TB-FAN") (pin "3") (pinfunction "3_3") (pintype "bidirectional"))
    )
    (net (code "36") (name "Net-(Q3-PadE)") (class "Default")
      (node (ref "Q3") (pin "E") (pinfunction "E_E") (pintype "passive"))
      (node (ref "TB-RELAY") (pin "3") (pinfunction "3_3") (pintype "bidirectional"))
    )
    (net (code "37") (name "Net-(R1-1)") (class "Default")
      (node (ref "R1") (pin "P$1") (pinfunction "1_P$1") (pintype "passive"))
      (node (ref "R2") (pin "P$2") (pinfunction "2_P$2") (pintype "passive"))
      (node (ref "U2") (pin "4") (pinfunction "PFI_4") (pintype "bidirectional"))
    )
    (net (code "38") (name "Net-(R3-1)") (class "Default")
      (node (ref "R3") (pin "P$1") (pinfunction "1_P$1") (pintype "passive"))
      (node (ref "U3") (pin "12") (pinfunction "O_12") (pintype "output"))
      (node (ref "U3") (pin "3") (pinfunction "I_3") (pintype "input"))
    )
    (net (code "39") (name "Net-(R3-2)") (class "Default")
      (node (ref "R3") (pin "P$2") (pinfunction "2_P$2") (pintype "passive"))
      (node (ref "TB2") (pin "1") (pinfunction "1_1") (pintype "bidirectional"))
      (node (ref "TB2") (pin "11") (pinfunction "1_11") (pintype "bidirectional"))
    )
    (net (code "40") (name "Net-(R4-1)") (class "Default")
      (node (ref "R4") (pin "P$1") (pinfunction "1_P$1") (pintype "passive"))
      (node (ref "U3") (pin "4") (pinfunction "O_4") (pintype "output"))
    )
    (net (code "41") (name "Net-(R4-2)") (class "Default")
      (node (ref "R4") (pin "P$2") (pinfunction "2_P$2") (pintype "passive"))
      (node (ref "TB2") (pin "12") (pinfunction "2_12") (pintype "bidirectional"))
      (node (ref "TB2") (pin "2") (pinfunction "2_2") (pintype "bidirectional"))
    )
    (net (code "42") (name "Net-(R5-1)") (class "Default")
      (node (ref "R5") (pin "P$1") (pinfunction "1_P$1") (pintype "passive"))
      (node (ref "U3") (pin "6") (pinfunction "O_6") (pintype "output"))
      (node (ref "U3") (pin "9") (pinfunction "I_9") (pintype "input"))
    )
    (net (code "43") (name "Net-(R5-2)") (class "Default")
      (node (ref "R5") (pin "P$2") (pinfunction "2_P$2") (pintype "passive"))
      (node (ref "TB2") (pin "13") (pinfunction "3_13") (pintype "bidirectional"))
      (node (ref "TB2") (pin "3") (pinfunction "3_3") (pintype "bidirectional"))
    )
    (net (code "44") (name "Net-(R6-1)") (class "Default")
      (node (ref "R6") (pin "P$1") (pinfunction "1_P$1") (pintype "passive"))
      (node (ref "U3") (pin "8") (pinfunction "O_8") (pintype "output"))
    )
    (net (code "45") (name "Net-(R6-2)") (class "Default")
      (node (ref "R6") (pin "P$2") (pinfunction "2_P$2") (pintype "passive"))
      (node (ref "TB2") (pin "14") (pinfunction "4_14") (pintype "bidirectional"))
      (node (ref "TB2") (pin "4") (pinfunction "4_4") (pintype "bidirectional"))
    )
    (net (code "46") (name "Net-(R7-1)") (class "Default")
      (node (ref "R7") (pin "P$1") (pinfunction "1_P$1") (pintype "passive"))
      (node (ref "U3") (pin "10") (pinfunction "O_10") (pintype "output"))
      (node (ref "U4") (pin "1") (pinfunction "I_1") (pintype "input"))
    )
    (net (code "47") (name "Net-(R7-2)") (class "Default")
      (node (ref "R7") (pin "P$2") (pinfunction "2_P$2") (pintype "passive"))
      (node (ref "TB3") (pin "1") (pinfunction "1_1") (pintype "bidirectional"))
      (node (ref "TB3") (pin "11") (pinfunction "1_11") (pintype "bidirectional"))
    )
    (net (code "48") (name "Net-(R8-1)") (class "Default")
      (node (ref "R8") (pin "P$1") (pinfunction "1_P$1") (pintype "passive"))
      (node (ref "U4") (pin "2") (pinfunction "O_2") (pintype "output"))
    )
    (net (code "49") (name "Net-(R8-2)") (class "Default")
      (node (ref "R8") (pin "P$2") (pinfunction "2_P$2") (pintype "passive"))
      (node (ref "TB3") (pin "12") (pinfunction "2_12") (pintype "bidirectional"))
      (node (ref "TB3") (pin "2") (pinfunction "2_2") (pintype "bidirectional"))
    )
    (net (code "50") (name "Net-(R9-1)") (class "Default")
      (node (ref "R9") (pin "P$1") (pinfunction "1_P$1") (pintype "passive"))
      (node (ref "U4") (pin "12") (pinfunction "O_12") (pintype "output"))
      (node (ref "U4") (pin "3") (pinfunction "I_3") (pintype "input"))
    )
    (net (code "51") (name "Net-(R9-2)") (class "Default")
      (node (ref "R9") (pin "P$2") (pinfunction "2_P$2") (pintype "passive"))
      (node (ref "TB3") (pin "13") (pinfunction "3_13") (pintype "bidirectional"))
      (node (ref "TB3") (pin "3") (pinfunction "3_3") (pintype "bidirectional"))
    )
    (net (code "52") (name "Net-(R10-1)") (class "Default")
      (node (ref "R10") (pin "P$1") (pinfunction "1_P$1") (pintype "passive"))
      (node (ref "U4") (pin "4") (pinfunction "O_4") (pintype "output"))
    )
    (net (code "53") (name "Net-(R10-2)") (class "Default")
      (node (ref "R10") (pin "P$2") (pinfunction "2_P$2") (pintype "passive"))
      (node (ref "TB3") (pin "14") (pinfunction "4_14") (pintype "bidirectional"))
      (node (ref "TB3") (pin "4") (pinfunction "4_4") (pintype "bidirectional"))
    )
    (net (code "54") (name "Net-(R11-1)") (class "Default")
      (node (ref "R11") (pin "P$1") (pinfunction "1_P$1") (pintype "passive"))
      (node (ref "U4") (pin "6") (pinfunction "O_6") (pintype "output"))
      (node (ref "U4") (pin "9") (pinfunction "I_9") (pintype "input"))
    )
    (net (code "55") (name "Net-(R11-2)") (class "Default")
      (node (ref "R11") (pin "P$2") (pinfunction "2_P$2") (pintype "passive"))
      (node (ref "TB4") (pin "1") (pinfunction "1_1") (pintype "bidirectional"))
      (node (ref "TB4") (pin "11") (pinfunction "1_11") (pintype "bidirectional"))
    )
    (net (code "56") (name "Net-(R12-1)") (class "Default")
      (node (ref "R12") (pin "P$1") (pinfunction "1_P$1") (pintype "passive"))
      (node (ref "U4") (pin "8") (pinfunction "O_8") (pintype "output"))
    )
    (net (code "57") (name "Net-(R12-2)") (class "Default")
      (node (ref "R12") (pin "P$2") (pinfunction "2_P$2") (pintype "passive"))
      (node (ref "TB4") (pin "12") (pinfunction "2_12") (pintype "bidirectional"))
      (node (ref "TB4") (pin "2") (pinfunction "2_2") (pintype "bidirectional"))
    )
    (net (code "58") (name "Net-(R13-1)") (class "Default")
      (node (ref "R13") (pin "P$1") (pinfunction "1_P$1") (pintype "passive"))
      (node (ref "U4") (pin "10") (pinfunction "O_10") (pintype "output"))
      (node (ref "U5") (pin "13") (pinfunction "I_13") (pintype "input"))
    )
    (net (code "59") (name "Net-(R13-2)") (class "Default")
      (node (ref "R13") (pin "P$2") (pinfunction "2_P$2") (pintype "passive"))
      (node (ref "TB4") (pin "13") (pinfunction "3_13") (pintype "bidirectional"))
      (node (ref "TB4") (pin "3") (pinfunction "3_3") (pintype "bidirectional"))
    )
    (net (code "60") (name "Net-(R14-1)") (class "Default")
      (node (ref "R14") (pin "P$1") (pinfunction "1_P$1") (pintype "passive"))
      (node (ref "U5") (pin "12") (pinfunction "O_12") (pintype "output"))
    )
    (net (code "61") (name "Net-(R14-2)") (class "Default")
      (node (ref "R14") (pin "P$2") (pinfunction "2_P$2") (pintype "passive"))
      (node (ref "TB4") (pin "14") (pinfunction "4_14") (pintype "bidirectional"))
      (node (ref "TB4") (pin "4") (pinfunction "4_4") (pintype "bidirectional"))
    )
    (net (code "62") (name "Net-(R15-1)") (class "Default")
      (node (ref "R15") (pin "P$1") (pinfunction "1_P$1") (pintype "passive"))
      (node (ref "U5") (pin "2") (pinfunction "O_2") (pintype "output"))
      (node (ref "U5") (pin "3") (pinfunction "I_3") (pintype "input"))
    )
    (net (code "63") (name "Net-(R15-2)") (class "Default")
      (node (ref "R15") (pin "P$2") (pinfunction "2_P$2") (pintype "passive"))
      (node (ref "TB5") (pin "1") (pinfunction "1_1") (pintype "bidirectional"))
      (node (ref "TB5") (pin "11") (pinfunction "1_11") (pintype "bidirectional"))
    )
    (net (code "64") (name "Net-(R16-1)") (class "Default")
      (node (ref "R16") (pin "P$1") (pinfunction "1_P$1") (pintype "passive"))
      (node (ref "U5") (pin "4") (pinfunction "O_4") (pintype "output"))
    )
    (net (code "65") (name "Net-(R16-2)") (class "Default")
      (node (ref "R16") (pin "P$2") (pinfunction "2_P$2") (pintype "passive"))
      (node (ref "TB5") (pin "12") (pinfunction "2_12") (pintype "bidirectional"))
      (node (ref "TB5") (pin "2") (pinfunction "2_2") (pintype "bidirectional"))
    )
    (net (code "66") (name "Net-(R17-1)") (class "Default")
      (node (ref "R17") (pin "P$1") (pinfunction "1_P$1") (pintype "passive"))
      (node (ref "U5") (pin "10") (pinfunction "O_10") (pintype "output"))
      (node (ref "U5") (pin "9") (pinfunction "I_9") (pintype "input"))
    )
    (net (code "67") (name "Net-(R17-2)") (class "Default")
      (node (ref "R17") (pin "P$2") (pinfunction "2_P$2") (pintype "passive"))
      (node (ref "TB5") (pin "13") (pinfunction "3_13") (pintype "bidirectional"))
      (node (ref "TB5") (pin "3") (pinfunction "3_3") (pintype "bidirectional"))
    )
    (net (code "68") (name "Net-(R18-1)") (class "Default")
      (node (ref "R18") (pin "P$1") (pinfunction "1_P$1") (pintype "passive"))
      (node (ref "U5") (pin "8") (pinfunction "O_8") (pintype "output"))
    )
    (net (code "69") (name "Net-(R18-2)") (class "Default")
      (node (ref "R18") (pin "P$2") (pinfunction "2_P$2") (pintype "passive"))
      (node (ref "TB5") (pin "14") (pinfunction "4_14") (pintype "bidirectional"))
      (node (ref "TB5") (pin "4") (pinfunction "4_4") (pintype "bidirectional"))
    )
    (net (code "70") (name "Net-(R19-1)") (class "Default")
      (node (ref "BI-LED") (pin "2") (pinfunction "2_2") (pintype "bidirectional"))
      (node (ref "R19") (pin "P$1") (pinfunction "1_P$1") (pintype "passive"))
      (node (ref "R20") (pin "P$2") (pinfunction "2_P$2") (pintype "passive"))
    )
    (net (code "71") (name "Net-(R21-1)") (class "Default")
      (node (ref "R21") (pin "P$1") (pinfunction "1_P$1") (pintype "passive"))
      (node (ref "R22") (pin "P$1") (pinfunction "1_P$1") (pintype "passive"))
      (node (ref "R40") (pin "E") (pinfunction "E_E") (pintype "passive"))
    )
    (net (code "72") (name "Net-(R21-2)") (class "Default")
      (node (ref "JP1") (pin "3") (pinfunction "3_3") (pintype "bidirectional"))
      (node (ref "R21") (pin "P$2") (pinfunction "2_P$2") (pintype "passive"))
    )
    (net (code "73") (name "Net-(R22-2)") (class "Default")
      (node (ref "JP1") (pin "1") (pinfunction "1_1") (pintype "bidirectional"))
      (node (ref "R22") (pin "P$2") (pinfunction "2_P$2") (pintype "passive"))
    )
    (net (code "74") (name "Net-(R23-2)") (class "Default")
      (node (ref "R23") (pin "P$2") (pinfunction "2_P$2") (pintype "passive"))
      (node (ref "R40") (pin "A") (pinfunction "A_A") (pintype "passive"))
    )
    (net (code "75") (name "Net-(R24-2)") (class "Default")
      (node (ref "C7") (pin "1") (pinfunction "1_1") (pintype "passive"))
      (node (ref "R24") (pin "P$2") (pinfunction "2_P$2") (pintype "passive"))
      (node (ref "R40") (pin "S") (pinfunction "S_S") (pintype "passive"))
    )
    (net (code "76") (name "Net-(R25-1)") (class "Default")
      (node (ref "J3") (pin "2") (pinfunction "2_2") (pintype "passive"))
      (node (ref "R25") (pin "P$1") (pinfunction "1_P$1") (pintype "passive"))
    )
    (net (code "77") (name "Net-(R25-2)") (class "Default")
      (node (ref "C10") (pin "1") (pinfunction "1_1") (pintype "passive"))
      (node (ref "R25") (pin "P$2") (pinfunction "2_P$2") (pintype "passive"))
      (node (ref "R26") (pin "P$2") (pinfunction "2_P$2") (pintype "passive"))
      (node (ref "R27") (pin "P$1") (pinfunction "1_P$1") (pintype "passive"))
    )
    (net (code "78") (name "Net-(R28-1)") (class "Default")
      (node (ref "J4") (pin "2") (pinfunction "2_2") (pintype "passive"))
      (node (ref "R28") (pin "P$1") (pinfunction "1_P$1") (pintype "passive"))
    )
    (net (code "79") (name "Net-(R28-2)") (class "Default")
      (node (ref "C11") (pin "1") (pinfunction "1_1") (pintype "passive"))
      (node (ref "R28") (pin "P$2") (pinfunction "2_P$2") (pintype "passive"))
      (node (ref "R29") (pin "P$2") (pinfunction "2_P$2") (pintype "passive"))
      (node (ref "R30") (pin "P$1") (pinfunction "1_P$1") (pintype "passive"))
    )
    (net (code "80") (name "Net-(R31-2)") (class "Default")
      (node (ref "J-AN2") (pin "2") (pinfunction "2_2") (pintype "passive"))
      (node (ref "R31") (pin "P$2") (pinfunction "2_P$2") (pintype "passive"))
    )
    (net (code "81") (name "Net-(R33-2)") (class "Default")
      (node (ref "J-SWON") (pin "1") (pinfunction "1_1") (pintype "passive"))
      (node (ref "R33") (pin "P$2") (pinfunction "2_P$2") (pintype "passive"))
    )
    (net (code "82") (name "Net-(R35-2)") (class "Default")
      (node (ref "J-SWOFF") (pin "1") (pinfunction "1_1") (pintype "passive"))
      (node (ref "R35") (pin "P$2") (pinfunction "2_P$2") (pintype "passive"))
    )
    (net (code "83") (name "Net-(R37-1)") (class "Default")
      (node (ref "J-SYNCIN") (pin "1") (pinfunction "1_1") (pintype "passive"))
      (node (ref "R37") (pin "P$1") (pinfunction "1_P$1") (pintype "passive"))
    )
    (net (code "84") (name "Net-(R41-1)") (class "Default")
      (node (ref "R41") (pin "P$1") (pinfunction "1_P$1") (pintype "passive"))
      (node (ref "T2") (pin "2") (pinfunction "B_2") (pintype "passive"))
    )
    (net (code "85") (name "Net-(R42-1)") (class "Default")
      (node (ref "Q1") (pin "S") (pinfunction "S_S") (pintype "passive"))
      (node (ref "Q2") (pin "S") (pinfunction "S_S") (pintype "passive"))
      (node (ref "R42") (pin "P$1") (pinfunction "1_P$1") (pintype "passive"))
      (node (ref "R44") (pin "P$1") (pinfunction "1_P$1") (pintype "passive"))
      (node (ref "TB-FAN") (pin "1") (pinfunction "1_1") (pintype "bidirectional"))
    )
    (net (code "86") (name "Net-(R42-2)") (class "Default")
      (node (ref "Q1") (pin "G") (pinfunction "G_G") (pintype "passive"))
      (node (ref "R42") (pin "P$2") (pinfunction "2_P$2") (pintype "passive"))
      (node (ref "T2") (pin "3") (pinfunction "C_3") (pintype "passive"))
    )
    (net (code "87") (name "Net-(R43-1)") (class "Default")
      (node (ref "R43") (pin "P$1") (pinfunction "1_P$1") (pintype "passive"))
      (node (ref "T3") (pin "2") (pinfunction "B_2") (pintype "passive"))
    )
    (net (code "88") (name "Net-(R44-2)") (class "Default")
      (node (ref "Q2") (pin "G") (pinfunction "G_G") (pintype "passive"))
      (node (ref "R44") (pin "P$2") (pinfunction "2_P$2") (pintype "passive"))
      (node (ref "T3") (pin "3") (pinfunction "C_3") (pintype "passive"))
    )
    (net (code "89") (name "Net-(R45-1)") (class "Default")
      (node (ref "J-50HZ") (pin "1") (pinfunction "1_1") (pintype "passive"))
      (node (ref "R45") (pin "P$1") (pinfunction "1_P$1") (pintype "passive"))
    )
    (net (code "90") (name "Net-(R45-2)") (class "Default")
      (node (ref "R45") (pin "P$2") (pinfunction "2_P$2") (pintype "passive"))
      (node (ref "U5") (pin "6") (pinfunction "O_6") (pintype "output"))
    )
    (net (code "91") (name "Net-(R46-1)") (class "Default")
      (node (ref "R46") (pin "P$1") (pinfunction "1_P$1") (pintype "passive"))
      (node (ref "U2") (pin "7") (pinfunction "-RESET_7") (pintype "bidirectional"))
    )
    (net (code "92") (name "Net-(U2--MR)") (class "Default")
      (node (ref "U2") (pin "1") (pinfunction "-MR_1") (pintype "bidirectional"))
      (node (ref "U2") (pin "5") (pinfunction "-PFO_5") (pintype "bidirectional"))
    )
    (net (code "93") (name "Net-(U3A-O)") (class "Default")
      (node (ref "BI-LED") (pin "1") (pinfunction "1_1") (pintype "bidirectional"))
      (node (ref "U3") (pin "2") (pinfunction "O_2") (pintype "output"))
    )
    (net (code "94") (name "OP-50HZ") (class "Default")
      (node (ref "U$1") (pin "25") (pinfunction "PA0_25") (pintype "bidirectional"))
      (node (ref "U5") (pin "5") (pinfunction "I_5") (pintype "input"))
    )
    (net (code "95") (name "OP-SYNCED") (class "Default")
      (node (ref "R39") (pin "P$2") (pinfunction "2_P$2") (pintype "passive"))
      (node (ref "U$1") (pin "5") (pinfunction "PA8_5") (pintype "bidirectional"))
    )
    (net (code "96") (name "PWM-FAN1") (class "Default")
      (node (ref "R41") (pin "P$2") (pinfunction "2_P$2") (pintype "passive"))
      (node (ref "U$1") (pin "28") (pinfunction "PA3_28") (pintype "bidirectional"))
    )
    (net (code "97") (name "PWM-FAN2") (class "Default")
      (node (ref "R43") (pin "P$2") (pinfunction "2_P$2") (pintype "passive"))
      (node (ref "U$1") (pin "27") (pinfunction "PA2_27") (pintype "bidirectional"))
    )
    (net (code "98") (name "RX1") (class "Default")
      (node (ref "J2") (pin "2") (pinfunction "2_2") (pintype "passive"))
      (node (ref "U$1") (pin "7") (pinfunction "PA10_7") (pintype "bidirectional"))
    )
    (net (code "99") (name "SCL1") (class "Default")
      (node (ref "U$1") (pin "14") (pinfunction "PB6_14") (pintype "bidirectional"))
    )
    (net (code "100") (name "SDA1") (class "Default")
      (node (ref "U$1") (pin "15") (pinfunction "PB7_15") (pintype "bidirectional"))
    )
    (net (code "101") (name "SMALL-L") (class "Default")
      (node (ref "U$1") (pin "35") (pinfunction "PB10_35") (pintype "bidirectional"))
      (node (ref "U3") (pin "11") (pinfunction "I_11") (pintype "input"))
    )
    (net (code "102") (name "SMALL-R") (class "Default")
      (node (ref "U$1") (pin "36") (pinfunction "PB11_36") (pintype "bidirectional"))
      (node (ref "U4") (pin "13") (pinfunction "I_13") (pintype "input"))
    )
    (net (code "103") (name "TINY-L") (class "Default")
      (node (ref "U$1") (pin "17") (pinfunction "PB9_17") (pintype "bidirectional"))
      (node (ref "U3") (pin "13") (pinfunction "I_13") (pintype "input"))
    )
    (net (code "104") (name "TINY-R") (class "Default")
      (node (ref "U$1") (pin "16") (pinfunction "PB8_16") (pintype "bidirectional"))
      (node (ref "U3") (pin "5") (pinfunction "I_5") (pintype "input"))
    )
    (net (code "105") (name "TX1") (class "Default")
      (node (ref "J2") (pin "3") (pinfunction "3_3") (pintype "passive"))
      (node (ref "U$1") (pin "6") (pinfunction "PA9_6") (pintype "bidirectional"))
    )
    (net (code "106") (name "unconnected-(TB-FAN-Pad4)") (class "Default")
      (node (ref "TB-FAN") (pin "4") (pinfunction "4_4") (pintype "bidirectional"))
    )
    (net (code "107") (name "unconnected-(U$1-PA11-Pad8)") (class "Default")
      (node (ref "U$1") (pin "8") (pinfunction "PA11_8") (pintype "bidirectional"))
    )
    (net (code "108") (name "unconnected-(U$1-PA12-Pad9)") (class "Default")
      (node (ref "U$1") (pin "9") (pinfunction "PA12_9") (pintype "bidirectional"))
    )
    (net (code "109") (name "unconnected-(U$1-VBAT-Pad21)") (class "Default")
      (node (ref "U$1") (pin "21") (pinfunction "VBAT_21") (pintype "bidirectional"))
    )
    (net (code "110") (name "unconnected-(U2--WDO-Pad8)") (class "Default")
      (node (ref "U2") (pin "8") (pinfunction "-WDO_8") (pintype "bidirectional"))
    )
    (net (code "111") (name "unconnected-(U2-WDI-Pad6)") (class "Default")
      (node (ref "U2") (pin "6") (pinfunction "WDI_6") (pintype "bidirectional"))
    )
  )
)
